# Displays.net
KiCad netlist of a schematic drawn in Altium Designer
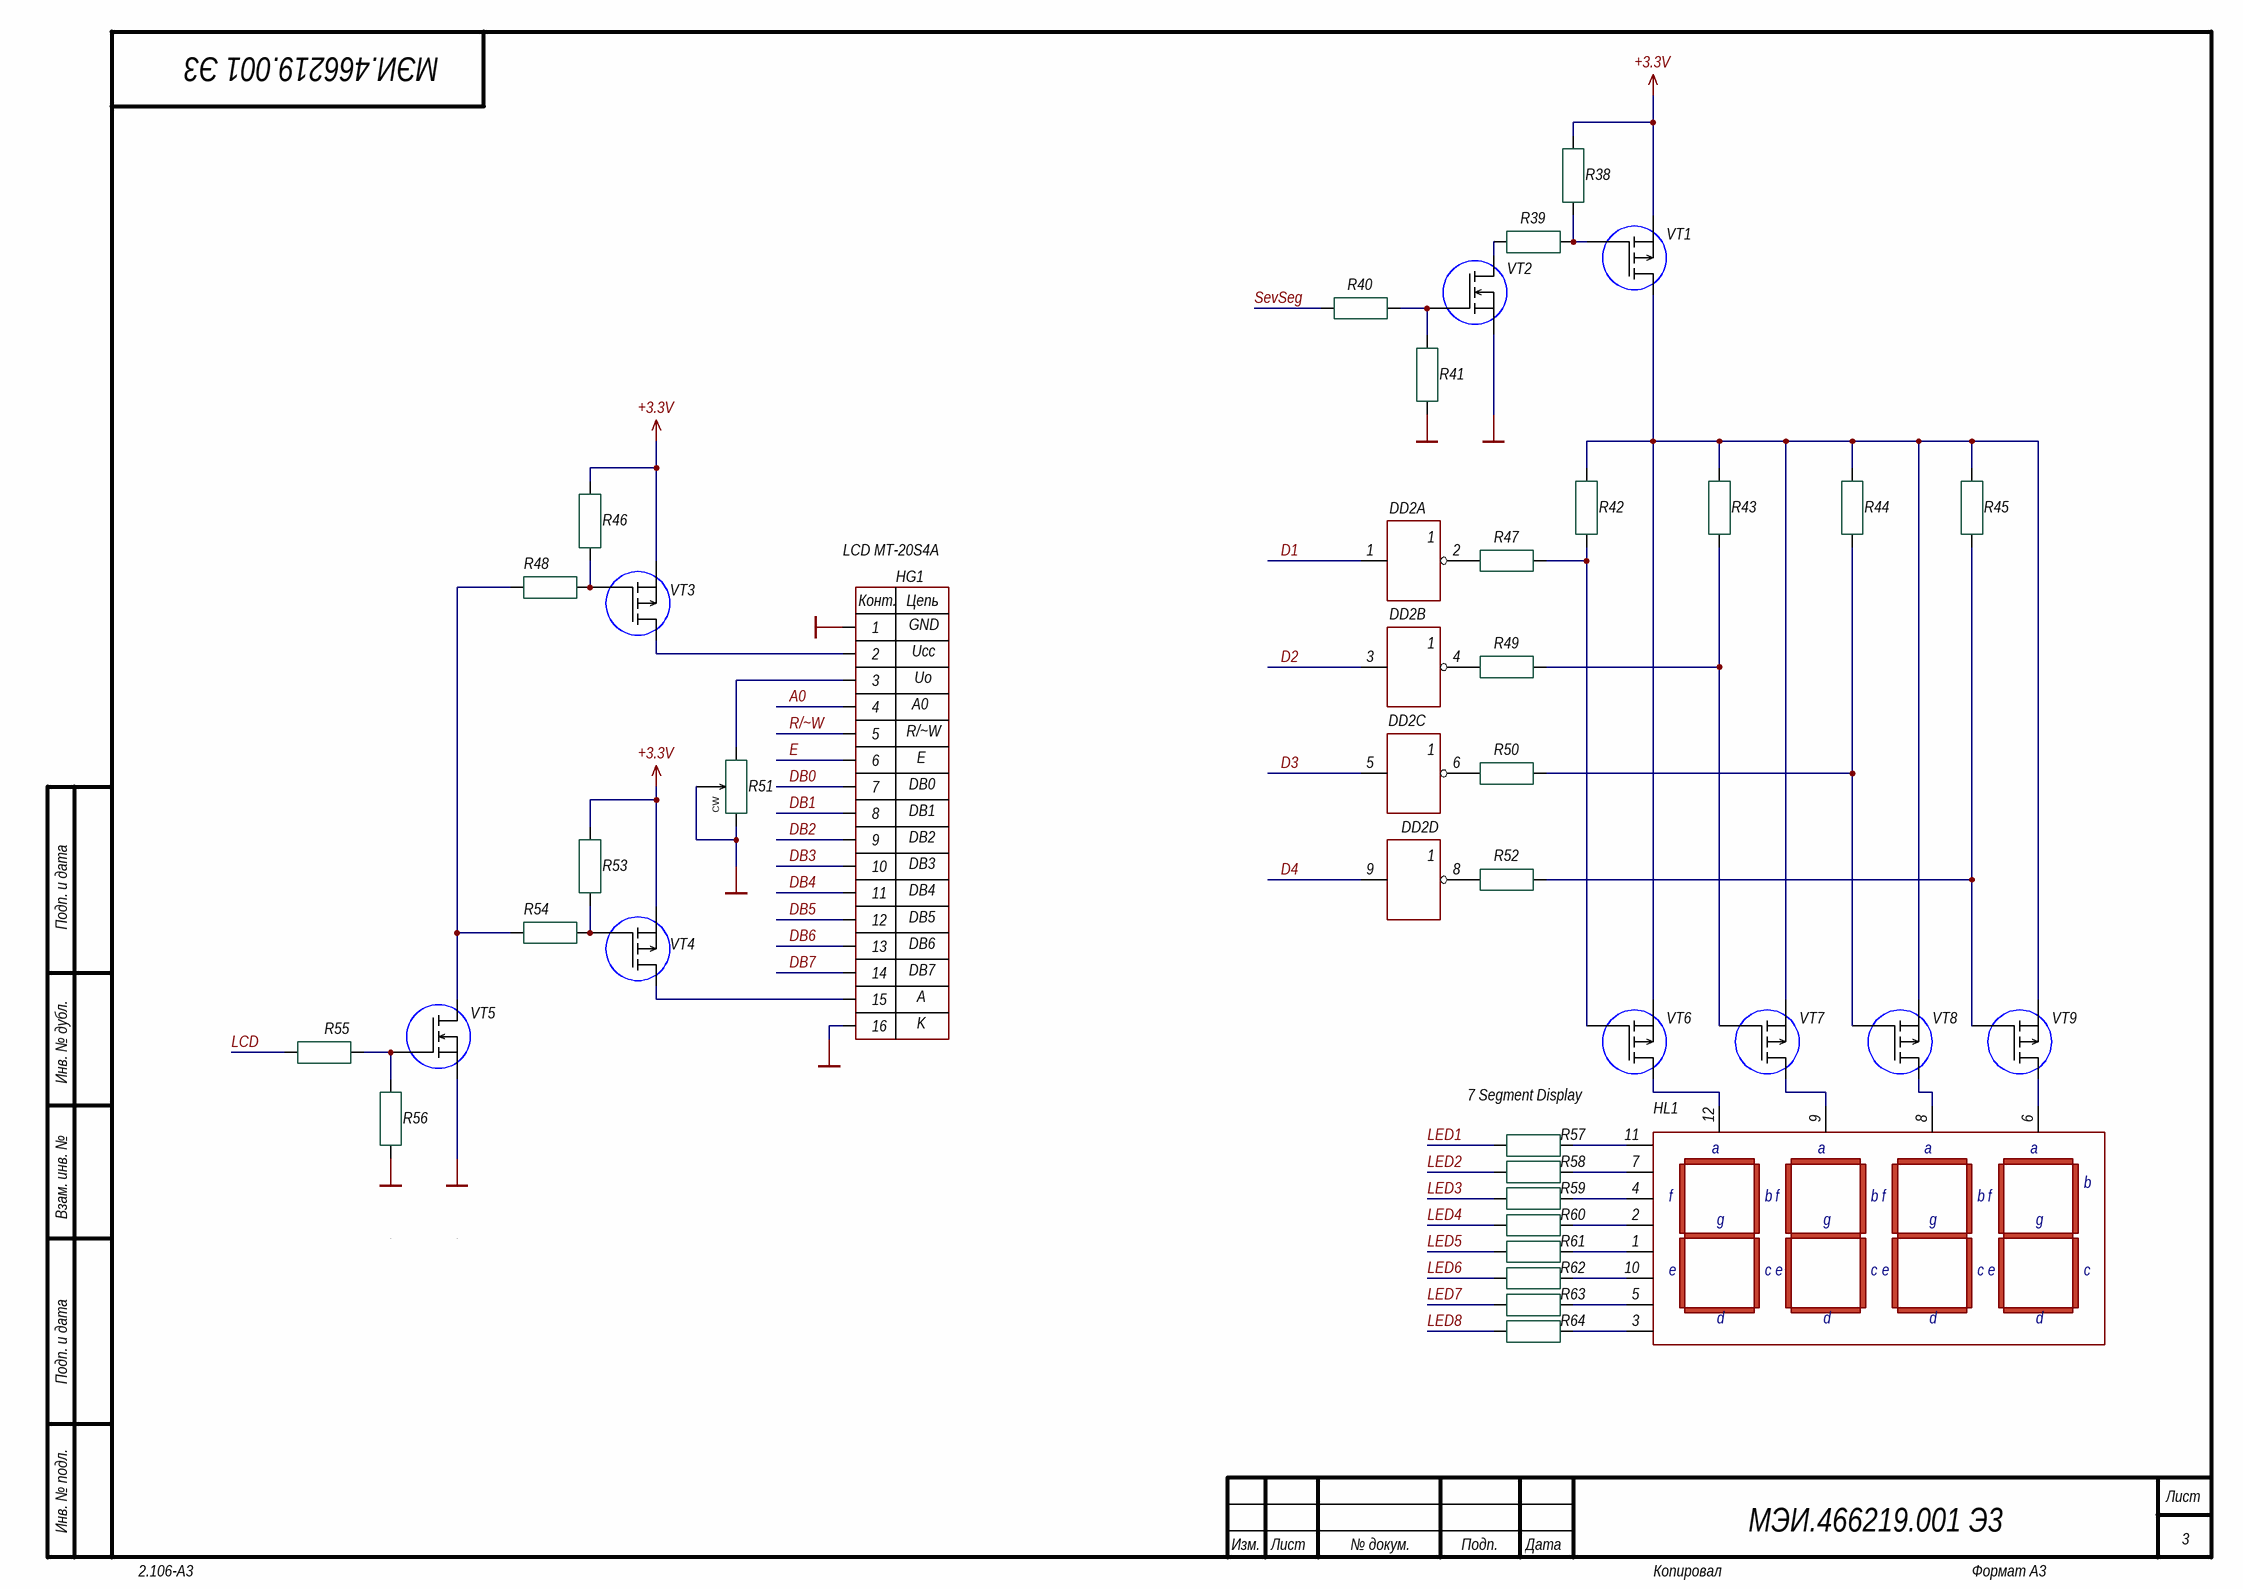
[diagram p0: Displays.SchDoc]

(export (version "E")
  (design (tool "Eeschema 10.0.6"))
  (components
    (comp (ref "DD2")
      (value "SN74AHCU04DR")
      (footprint "PBL - SMD Packages:SOIC127P780X200-14N")
      (description "HEX invertor")
      (libsource (lib "LeSta") (part "SN74AHCU04"))
    )
    (comp (ref "HG1")
      (value "MT-20S4A-2YLG-3V0")
      (footprint "LeSta:MT-20S4A")
      (description "LCD")
      (libsource (lib "LeSta") (part "MT-20S4A-2YLG-3V0"))
    )
    (comp (ref "HL1")
      (value "CA56-12GWA")
      (footprint "LeSta:CA56-12GWA")
      (description "Indicator")
      (libsource (lib "LeSta") (part "CA56-12GWA"))
    )
    (comp (ref "R38")
      (value "Thick Film")
      (footprint "RESC1608X55N")
      (description "Resistor SMD chip 10k Ohm 0.1W 1% 0603")
      (fields (field (name "TOLERANCE") "±1%"))
      (libsource (lib "PBL - Resistors") (part "RES_10K_0603_1%"))
    )
    (comp (ref "R39")
      (value "Thick Film")
      (footprint "RESC1608X55N")
      (description "Resistor SMD chip 470 Ohm 0.1W 5% 0603")
      (fields (field (name "TOLERANCE") "±5%"))
      (libsource (lib "PBL - Resistors") (part "RES_470R_0603_5%"))
    )
    (comp (ref "R40")
      (value "Thick Film")
      (footprint "RESC1608X55N")
      (description "Resistor SMD chip 470 Ohm 0.1W 5% 0603")
      (fields (field (name "TOLERANCE") "±5%"))
      (libsource (lib "PBL - Resistors") (part "RES_470R_0603_5%"))
    )
    (comp (ref "R41")
      (value "Thick Film")
      (footprint "RESC1608X55N")
      (description "Resistor SMD chip 10k Ohm 0.1W 1% 0603")
      (fields (field (name "TOLERANCE") "±1%"))
      (libsource (lib "PBL - Resistors") (part "RES_10K_0603_1%"))
    )
    (comp (ref "R42")
      (value "Thick Film")
      (footprint "RESC1608X55N")
      (description "Resistor SMD chip 10k Ohm 0.1W 1% 0603")
      (fields (field (name "TOLERANCE") "±1%"))
      (libsource (lib "PBL - Resistors") (part "RES_10K_0603_1%"))
    )
    (comp (ref "R43")
      (value "Thick Film")
      (footprint "RESC1608X55N")
      (description "Resistor SMD chip 10k Ohm 0.1W 1% 0603")
      (fields (field (name "TOLERANCE") "±1%"))
      (libsource (lib "PBL - Resistors") (part "RES_10K_0603_1%"))
    )
    (comp (ref "R44")
      (value "Thick Film")
      (footprint "RESC1608X55N")
      (description "Resistor SMD chip 10k Ohm 0.1W 1% 0603")
      (fields (field (name "TOLERANCE") "±1%"))
      (libsource (lib "PBL - Resistors") (part "RES_10K_0603_1%"))
    )
    (comp (ref "R45")
      (value "Thick Film")
      (footprint "RESC1608X55N")
      (description "Resistor SMD chip 10k Ohm 0.1W 1% 0603")
      (fields (field (name "TOLERANCE") "±1%"))
      (libsource (lib "PBL - Resistors") (part "RES_10K_0603_1%"))
    )
    (comp (ref "R46")
      (value "Thick Film")
      (footprint "RESC1608X55N")
      (description "Resistor SMD chip 10k Ohm 0.1W 1% 0603")
      (fields (field (name "TOLERANCE") "±1%"))
      (libsource (lib "PBL - Resistors") (part "RES_10K_0603_1%"))
    )
    (comp (ref "R47")
      (value "Thick Film")
      (footprint "RESC1608X55N")
      (description "Resistor SMD chip 470 Ohm 0.1W 5% 0603")
      (fields (field (name "TOLERANCE") "±5%"))
      (libsource (lib "PBL - Resistors") (part "RES_470R_0603_5%"))
    )
    (comp (ref "R48")
      (value "Thick Film")
      (footprint "RESC1608X55N")
      (description "Resistor SMD chip 470 Ohm 0.1W 5% 0603")
      (fields (field (name "TOLERANCE") "±5%"))
      (libsource (lib "PBL - Resistors") (part "RES_470R_0603_5%"))
    )
    (comp (ref "R49")
      (value "Thick Film")
      (footprint "RESC1608X55N")
      (description "Resistor SMD chip 470 Ohm 0.1W 5% 0603")
      (fields (field (name "TOLERANCE") "±5%"))
      (libsource (lib "PBL - Resistors") (part "RES_470R_0603_5%"))
    )
    (comp (ref "R50")
      (value "Thick Film")
      (footprint "RESC1608X55N")
      (description "Resistor SMD chip 470 Ohm 0.1W 5% 0603")
      (fields (field (name "TOLERANCE") "±5%"))
      (libsource (lib "PBL - Resistors") (part "RES_470R_0603_5%"))
    )
    (comp (ref "R51")
      (value "25 turns")
      (footprint "PBL - THD Packages:TrimPot_LCD")
      (description "Trimmer THD 10K 500mW 25-turn")
      (fields (field (name "TOLERANCE") "±10%"))
      (libsource (lib "PBL - Resistors") (part "RES_TRIMMER_10K_LCD"))
    )
    (comp (ref "R52")
      (value "Thick Film")
      (footprint "RESC1608X55N")
      (description "Resistor SMD chip 470 Ohm 0.1W 5% 0603")
      (fields (field (name "TOLERANCE") "±5%"))
      (libsource (lib "PBL - Resistors") (part "RES_470R_0603_5%"))
    )
    (comp (ref "R53")
      (value "Thick Film")
      (footprint "RESC1608X55N")
      (description "Resistor SMD chip 10k Ohm 0.1W 1% 0603")
      (fields (field (name "TOLERANCE") "±1%"))
      (libsource (lib "PBL - Resistors") (part "RES_10K_0603_1%"))
    )
    (comp (ref "R54")
      (value "Thick Film")
      (footprint "RESC1608X55N")
      (description "Resistor SMD chip 470 Ohm 0.1W 5% 0603")
      (fields (field (name "TOLERANCE") "±5%"))
      (libsource (lib "PBL - Resistors") (part "RES_470R_0603_5%"))
    )
    (comp (ref "R55")
      (value "Thick Film")
      (footprint "RESC1608X55N")
      (description "Resistor SMD chip 470 Ohm 0.1W 5% 0603")
      (fields (field (name "TOLERANCE") "±5%"))
      (libsource (lib "PBL - Resistors") (part "RES_470R_0603_5%"))
    )
    (comp (ref "R56")
      (value "Thick Film")
      (footprint "RESC1608X55N")
      (description "Resistor SMD chip 10k Ohm 0.1W 1% 0603")
      (fields (field (name "TOLERANCE") "±1%"))
      (libsource (lib "PBL - Resistors") (part "RES_10K_0603_1%"))
    )
    (comp (ref "R57")
      (value "Thick Film")
      (footprint "RESC1608X55N")
      (description "Resistor SMD chip 68 Ohm 0.1W 5% 0603")
      (fields (field (name "TOLERANCE") "±1%"))
      (libsource (lib "PBL - Resistors") (part "RES_68R_0603_5%"))
    )
    (comp (ref "R58")
      (value "Thick Film")
      (footprint "RESC1608X55N")
      (description "Resistor SMD chip 68 Ohm 0.1W 5% 0603")
      (fields (field (name "TOLERANCE") "±1%"))
      (libsource (lib "PBL - Resistors") (part "RES_68R_0603_5%"))
    )
    (comp (ref "R59")
      (value "Thick Film")
      (footprint "RESC1608X55N")
      (description "Resistor SMD chip 68 Ohm 0.1W 5% 0603")
      (fields (field (name "TOLERANCE") "±1%"))
      (libsource (lib "PBL - Resistors") (part "RES_68R_0603_5%"))
    )
    (comp (ref "R60")
      (value "Thick Film")
      (footprint "RESC1608X55N")
      (description "Resistor SMD chip 68 Ohm 0.1W 5% 0603")
      (fields (field (name "TOLERANCE") "±1%"))
      (libsource (lib "PBL - Resistors") (part "RES_68R_0603_5%"))
    )
    (comp (ref "R61")
      (value "Thick Film")
      (footprint "RESC1608X55N")
      (description "Resistor SMD chip 68 Ohm 0.1W 5% 0603")
      (fields (field (name "TOLERANCE") "±1%"))
      (libsource (lib "PBL - Resistors") (part "RES_68R_0603_5%"))
    )
    (comp (ref "R62")
      (value "Thick Film")
      (footprint "RESC1608X55N")
      (description "Resistor SMD chip 68 Ohm 0.1W 5% 0603")
      (fields (field (name "TOLERANCE") "±1%"))
      (libsource (lib "PBL - Resistors") (part "RES_68R_0603_5%"))
    )
    (comp (ref "R63")
      (value "Thick Film")
      (footprint "RESC1608X55N")
      (description "Resistor SMD chip 68 Ohm 0.1W 5% 0603")
      (fields (field (name "TOLERANCE") "±1%"))
      (libsource (lib "PBL - Resistors") (part "RES_68R_0603_5%"))
    )
    (comp (ref "R64")
      (value "Thick Film")
      (footprint "RESC1608X55N")
      (description "Resistor SMD chip 68 Ohm 0.1W 5% 0603")
      (fields (field (name "TOLERANCE") "±1%"))
      (libsource (lib "PBL - Resistors") (part "RES_68R_0603_5%"))
    )
    (comp (ref "VT1")
      (value "IRLML2244")
      (footprint "PBL - SMD Packages:SOT23-3-no_check")
      (description "MOSFET P-Channel SMD")
      (libsource (lib "PBL - Transistors") (part "MOSFET_P-CH_IRLML2244TRPbF"))
    )
    (comp (ref "VT2")
      (value "IRLML6244")
      (footprint "PBL - SMD Packages:SOT23-3-no_check")
      (description "MOSFET N-Channel SMD")
      (libsource (lib "PBL - Transistors") (part "MOSFET_N-CH_IRLML6244TRPBF"))
    )
    (comp (ref "VT3")
      (value "IRLML2244")
      (footprint "PBL - SMD Packages:SOT23-3-no_check")
      (description "MOSFET P-Channel SMD")
      (libsource (lib "PBL - Transistors") (part "MOSFET_P-CH_IRLML2244TRPbF"))
    )
    (comp (ref "VT4")
      (value "IRLML2244")
      (footprint "PBL - SMD Packages:SOT23-3-no_check")
      (description "MOSFET P-Channel SMD")
      (libsource (lib "PBL - Transistors") (part "MOSFET_P-CH_IRLML2244TRPbF"))
    )
    (comp (ref "VT5")
      (value "IRLML6244")
      (footprint "PBL - SMD Packages:SOT23-3-no_check")
      (description "MOSFET N-Channel SMD")
      (libsource (lib "PBL - Transistors") (part "MOSFET_N-CH_IRLML6244TRPBF"))
    )
    (comp (ref "VT6")
      (value "IRLML2244")
      (footprint "PBL - SMD Packages:SOT23-3-no_check")
      (description "MOSFET P-Channel SMD")
      (libsource (lib "PBL - Transistors") (part "MOSFET_P-CH_IRLML2244TRPbF"))
    )
    (comp (ref "VT7")
      (value "IRLML2244")
      (footprint "PBL - SMD Packages:SOT23-3-no_check")
      (description "MOSFET P-Channel SMD")
      (libsource (lib "PBL - Transistors") (part "MOSFET_P-CH_IRLML2244TRPbF"))
    )
    (comp (ref "VT8")
      (value "IRLML2244")
      (footprint "PBL - SMD Packages:SOT23-3-no_check")
      (description "MOSFET P-Channel SMD")
      (libsource (lib "PBL - Transistors") (part "MOSFET_P-CH_IRLML2244TRPbF"))
    )
    (comp (ref "VT9")
      (value "IRLML2244")
      (footprint "PBL - SMD Packages:SOT23-3-no_check")
      (description "MOSFET P-Channel SMD")
      (libsource (lib "PBL - Transistors") (part "MOSFET_P-CH_IRLML2244TRPbF"))
    )
    (comp (ref "X13")
      (value "PBS-16R")
      (footprint "LeSta:PBS16")
      (description "CONN LCD")
      (libsource (lib "LeSta") (part "CONN LCD"))
    )
    (comp (ref "X14")
      (value "PBS-16R")
      (footprint "LeSta:PBS16")
      (description "CONN LCD")
      (libsource (lib "LeSta") (part "CONN LCD"))
    )
  )
  (nets
    (net (code "1") (name "+3.3V") (class "Default")
      (node (ref "R38") (pin "2") (pinfunction "2_2") (pintype "passive"))
      (node (ref "R46") (pin "2") (pinfunction "2_2") (pintype "passive"))
      (node (ref "R53") (pin "2") (pinfunction "2_2") (pintype "passive"))
      (node (ref "VT1") (pin "2") (pinfunction "S_2") (pintype "passive"))
      (node (ref "VT3") (pin "2") (pinfunction "S_2") (pintype "passive"))
      (node (ref "VT4") (pin "2") (pinfunction "S_2") (pintype "passive"))
    )
    (net (code "2") (name "/A0") (class "Default")
      (node (ref "HG1") (pin "4") (pinfunction "4_4") (pintype "passive"))
    )
    (net (code "3") (name "/D1") (class "Default")
      (node (ref "DD2") (pin "1") (pinfunction "1A_1") (pintype "passive"))
    )
    (net (code "4") (name "/D2") (class "Default")
      (node (ref "DD2") (pin "3") (pinfunction "2A_3") (pintype "passive"))
    )
    (net (code "5") (name "/D3") (class "Default")
      (node (ref "DD2") (pin "5") (pinfunction "3A_5") (pintype "passive"))
    )
    (net (code "6") (name "/D4") (class "Default")
      (node (ref "DD2") (pin "9") (pinfunction "4A_9") (pintype "passive"))
    )
    (net (code "7") (name "/DB0") (class "Default")
      (node (ref "HG1") (pin "7") (pinfunction "7_7") (pintype "passive"))
    )
    (net (code "8") (name "/DB1") (class "Default")
      (node (ref "HG1") (pin "8") (pinfunction "8_8") (pintype "passive"))
    )
    (net (code "9") (name "/DB2") (class "Default")
      (node (ref "HG1") (pin "9") (pinfunction "9_9") (pintype "passive"))
    )
    (net (code "10") (name "/DB3") (class "Default")
      (node (ref "HG1") (pin "10") (pinfunction "10_10") (pintype "passive"))
    )
    (net (code "11") (name "/DB4") (class "Default")
      (node (ref "HG1") (pin "11") (pinfunction "11_11") (pintype "passive"))
    )
    (net (code "12") (name "/DB5") (class "Default")
      (node (ref "HG1") (pin "12") (pinfunction "12_12") (pintype "passive"))
    )
    (net (code "13") (name "/DB6") (class "Default")
      (node (ref "HG1") (pin "13") (pinfunction "13_13") (pintype "passive"))
    )
    (net (code "14") (name "/DB7") (class "Default")
      (node (ref "HG1") (pin "14") (pinfunction "14_14") (pintype "passive"))
    )
    (net (code "15") (name "/E") (class "Default")
      (node (ref "HG1") (pin "6") (pinfunction "6_6") (pintype "passive"))
    )
    (net (code "16") (name "/LCD") (class "Default")
      (node (ref "R55") (pin "1") (pinfunction "1_1") (pintype "passive"))
    )
    (net (code "17") (name "/LED1") (class "Default")
      (node (ref "R57") (pin "1") (pinfunction "1_1") (pintype "passive"))
    )
    (net (code "18") (name "/LED2") (class "Default")
      (node (ref "R58") (pin "1") (pinfunction "1_1") (pintype "passive"))
    )
    (net (code "19") (name "/LED3") (class "Default")
      (node (ref "R59") (pin "1") (pinfunction "1_1") (pintype "passive"))
    )
    (net (code "20") (name "/LED4") (class "Default")
      (node (ref "R60") (pin "1") (pinfunction "1_1") (pintype "passive"))
    )
    (net (code "21") (name "/LED5") (class "Default")
      (node (ref "R61") (pin "1") (pinfunction "1_1") (pintype "passive"))
    )
    (net (code "22") (name "/LED6") (class "Default")
      (node (ref "R62") (pin "1") (pinfunction "1_1") (pintype "passive"))
    )
    (net (code "23") (name "/LED7") (class "Default")
      (node (ref "R63") (pin "1") (pinfunction "1_1") (pintype "passive"))
    )
    (net (code "24") (name "/LED8") (class "Default")
      (node (ref "R64") (pin "1") (pinfunction "1_1") (pintype "passive"))
    )
    (net (code "25") (name "/R{slash}~W") (class "Default")
      (node (ref "HG1") (pin "5") (pinfunction "5_5") (pintype "passive"))
    )
    (net (code "26") (name "/SevSeg") (class "Default")
      (node (ref "R40") (pin "1") (pinfunction "1_1") (pintype "passive"))
    )
    (net (code "27") (name "GND") (class "Default")
      (node (ref "HG1") (pin "1") (pinfunction "1_1") (pintype "passive"))
      (node (ref "HG1") (pin "16") (pinfunction "16_16") (pintype "passive"))
      (node (ref "R41") (pin "1") (pinfunction "1_1") (pintype "passive"))
      (node (ref "R51") (pin "CW") (pinfunction "1_CW") (pintype "passive"))
      (node (ref "R51") (pin "W") (pinfunction "W_W") (pintype "passive"))
      (node (ref "R56") (pin "1") (pinfunction "1_1") (pintype "passive"))
      (node (ref "VT2") (pin "2") (pinfunction "S_2") (pintype "passive"))
      (node (ref "VT5") (pin "2") (pinfunction "S_2") (pintype "passive"))
    )
    (net (code "28") (name "Net-(DD2A-1Y)") (class "Default")
      (node (ref "DD2") (pin "2") (pinfunction "1Y_2") (pintype "passive"))
      (node (ref "R47") (pin "1") (pinfunction "1_1") (pintype "passive"))
    )
    (net (code "29") (name "Net-(DD2B-2Y)") (class "Default")
      (node (ref "DD2") (pin "4") (pinfunction "2Y_4") (pintype "passive"))
      (node (ref "R49") (pin "1") (pinfunction "1_1") (pintype "passive"))
    )
    (net (code "30") (name "Net-(DD2C-3Y)") (class "Default")
      (node (ref "DD2") (pin "6") (pinfunction "3Y_6") (pintype "passive"))
      (node (ref "R50") (pin "1") (pinfunction "1_1") (pintype "passive"))
    )
    (net (code "31") (name "Net-(DD2D-4Y)") (class "Default")
      (node (ref "DD2") (pin "8") (pinfunction "4Y_8") (pintype "passive"))
      (node (ref "R52") (pin "1") (pinfunction "1_1") (pintype "passive"))
    )
    (net (code "32") (name "Net-(HL1-DP)") (class "Default")
      (node (ref "HL1") (pin "3") (pinfunction "DP_3") (pintype "passive"))
      (node (ref "R64") (pin "2") (pinfunction "2_2") (pintype "passive"))
    )
    (net (code "33") (name "Net-(HL1-Dig1)") (class "Default")
      (node (ref "HL1") (pin "12") (pinfunction "Dig1_12") (pintype "passive"))
      (node (ref "VT6") (pin "3") (pinfunction "D_3") (pintype "passive"))
    )
    (net (code "34") (name "Net-(HL1-Dig2)") (class "Default")
      (node (ref "HL1") (pin "9") (pinfunction "Dig2_9") (pintype "passive"))
      (node (ref "VT7") (pin "3") (pinfunction "D_3") (pintype "passive"))
    )
    (net (code "35") (name "Net-(HL1-Dig3)") (class "Default")
      (node (ref "HL1") (pin "8") (pinfunction "Dig3_8") (pintype "passive"))
      (node (ref "VT8") (pin "3") (pinfunction "D_3") (pintype "passive"))
    )
    (net (code "36") (name "Net-(HL1-Dig4)") (class "Default")
      (node (ref "HL1") (pin "6") (pinfunction "Dig4_6") (pintype "passive"))
      (node (ref "VT9") (pin "3") (pinfunction "D_3") (pintype "passive"))
    )
    (net (code "37") (name "Net-(HL1-a)") (class "Default")
      (node (ref "HL1") (pin "11") (pinfunction "a_11") (pintype "passive"))
      (node (ref "R57") (pin "2") (pinfunction "2_2") (pintype "passive"))
    )
    (net (code "38") (name "Net-(HL1-b)") (class "Default")
      (node (ref "HL1") (pin "7") (pinfunction "b_7") (pintype "passive"))
      (node (ref "R58") (pin "2") (pinfunction "2_2") (pintype "passive"))
    )
    (net (code "39") (name "Net-(HL1-c)") (class "Default")
      (node (ref "HL1") (pin "4") (pinfunction "c_4") (pintype "passive"))
      (node (ref "R59") (pin "2") (pinfunction "2_2") (pintype "passive"))
    )
    (net (code "40") (name "Net-(HL1-d)") (class "Default")
      (node (ref "HL1") (pin "2") (pinfunction "d_2") (pintype "passive"))
      (node (ref "R60") (pin "2") (pinfunction "2_2") (pintype "passive"))
    )
    (net (code "41") (name "Net-(HL1-e)") (class "Default")
      (node (ref "HL1") (pin "1") (pinfunction "e_1") (pintype "passive"))
      (node (ref "R61") (pin "2") (pinfunction "2_2") (pintype "passive"))
    )
    (net (code "42") (name "Net-(HL1-f)") (class "Default")
      (node (ref "HL1") (pin "10") (pinfunction "f_10") (pintype "passive"))
      (node (ref "R62") (pin "2") (pinfunction "2_2") (pintype "passive"))
    )
    (net (code "43") (name "Net-(HL1-g)") (class "Default")
      (node (ref "HL1") (pin "5") (pinfunction "g_5") (pintype "passive"))
      (node (ref "R63") (pin "2") (pinfunction "2_2") (pintype "passive"))
    )
    (net (code "44") (name "Net-(R51-2)") (class "Default")
      (node (ref "HG1") (pin "3") (pinfunction "3_3") (pintype "passive"))
      (node (ref "R51") (pin "CCW") (pinfunction "2_CCW") (pintype "passive"))
    )
    (net (code "45") (name "Net-(VT1-D)") (class "Default")
      (node (ref "R42") (pin "2") (pinfunction "2_2") (pintype "passive"))
      (node (ref "R43") (pin "2") (pinfunction "2_2") (pintype "passive"))
      (node (ref "R44") (pin "2") (pinfunction "2_2") (pintype "passive"))
      (node (ref "R45") (pin "2") (pinfunction "2_2") (pintype "passive"))
      (node (ref "VT1") (pin "3") (pinfunction "D_3") (pintype "passive"))
      (node (ref "VT6") (pin "2") (pinfunction "S_2") (pintype "passive"))
      (node (ref "VT7") (pin "2") (pinfunction "S_2") (pintype "passive"))
      (node (ref "VT8") (pin "2") (pinfunction "S_2") (pintype "passive"))
      (node (ref "VT9") (pin "2") (pinfunction "S_2") (pintype "passive"))
    )
    (net (code "46") (name "Net-(VT1-G)") (class "Default")
      (node (ref "R38") (pin "1") (pinfunction "1_1") (pintype "passive"))
      (node (ref "R39") (pin "2") (pinfunction "2_2") (pintype "passive"))
      (node (ref "VT1") (pin "1") (pinfunction "G_1") (pintype "passive"))
    )
    (net (code "47") (name "Net-(VT2-D)") (class "Default")
      (node (ref "R39") (pin "1") (pinfunction "1_1") (pintype "passive"))
      (node (ref "VT2") (pin "3") (pinfunction "D_3") (pintype "passive"))
    )
    (net (code "48") (name "Net-(VT2-G)") (class "Default")
      (node (ref "R40") (pin "2") (pinfunction "2_2") (pintype "passive"))
      (node (ref "R41") (pin "2") (pinfunction "2_2") (pintype "passive"))
      (node (ref "VT2") (pin "1") (pinfunction "G_1") (pintype "passive"))
    )
    (net (code "49") (name "Net-(VT3-D)") (class "Default")
      (node (ref "HG1") (pin "2") (pinfunction "2_2") (pintype "passive"))
      (node (ref "VT3") (pin "3") (pinfunction "D_3") (pintype "passive"))
    )
    (net (code "50") (name "Net-(VT3-G)") (class "Default")
      (node (ref "R46") (pin "1") (pinfunction "1_1") (pintype "passive"))
      (node (ref "R48") (pin "2") (pinfunction "2_2") (pintype "passive"))
      (node (ref "VT3") (pin "1") (pinfunction "G_1") (pintype "passive"))
    )
    (net (code "51") (name "Net-(VT4-D)") (class "Default")
      (node (ref "HG1") (pin "15") (pinfunction "15_15") (pintype "passive"))
      (node (ref "VT4") (pin "3") (pinfunction "D_3") (pintype "passive"))
    )
    (net (code "52") (name "Net-(VT4-G)") (class "Default")
      (node (ref "R53") (pin "1") (pinfunction "1_1") (pintype "passive"))
      (node (ref "R54") (pin "2") (pinfunction "2_2") (pintype "passive"))
      (node (ref "VT4") (pin "1") (pinfunction "G_1") (pintype "passive"))
    )
    (net (code "53") (name "Net-(VT5-D)") (class "Default")
      (node (ref "R48") (pin "1") (pinfunction "1_1") (pintype "passive"))
      (node (ref "R54") (pin "1") (pinfunction "1_1") (pintype "passive"))
      (node (ref "VT5") (pin "3") (pinfunction "D_3") (pintype "passive"))
    )
    (net (code "54") (name "Net-(VT5-G)") (class "Default")
      (node (ref "R55") (pin "2") (pinfunction "2_2") (pintype "passive"))
      (node (ref "R56") (pin "2") (pinfunction "2_2") (pintype "passive"))
      (node (ref "VT5") (pin "1") (pinfunction "G_1") (pintype "passive"))
    )
    (net (code "55") (name "Net-(VT6-G)") (class "Default")
      (node (ref "R42") (pin "1") (pinfunction "1_1") (pintype "passive"))
      (node (ref "R47") (pin "2") (pinfunction "2_2") (pintype "passive"))
      (node (ref "VT6") (pin "1") (pinfunction "G_1") (pintype "passive"))
    )
    (net (code "56") (name "Net-(VT7-G)") (class "Default")
      (node (ref "R43") (pin "1") (pinfunction "1_1") (pintype "passive"))
      (node (ref "R49") (pin "2") (pinfunction "2_2") (pintype "passive"))
      (node (ref "VT7") (pin "1") (pinfunction "G_1") (pintype "passive"))
    )
    (net (code "57") (name "Net-(VT8-G)") (class "Default")
      (node (ref "R44") (pin "1") (pinfunction "1_1") (pintype "passive"))
      (node (ref "R50") (pin "2") (pinfunction "2_2") (pintype "passive"))
      (node (ref "VT8") (pin "1") (pinfunction "G_1") (pintype "passive"))
    )
    (net (code "58") (name "Net-(VT9-G)") (class "Default")
      (node (ref "R45") (pin "1") (pinfunction "1_1") (pintype "passive"))
      (node (ref "R52") (pin "2") (pinfunction "2_2") (pintype "passive"))
      (node (ref "VT9") (pin "1") (pinfunction "G_1") (pintype "passive"))
    )
    (net (code "59") (name "unconnected-(X13-VCC-Pad1)") (class "Default")
      (node (ref "X13") (pin "1") (pinfunction "VCC_1") (pintype "passive"))
    )
    (net (code "60") (name "unconnected-(X14-VCC-Pad1)") (class "Default")
      (node (ref "X14") (pin "1") (pinfunction "VCC_1") (pintype "passive"))
    )
  )
)
